# ultrasonic_motion_sensor.net
KiCad netlist of a schematic drawn in EasyEDA
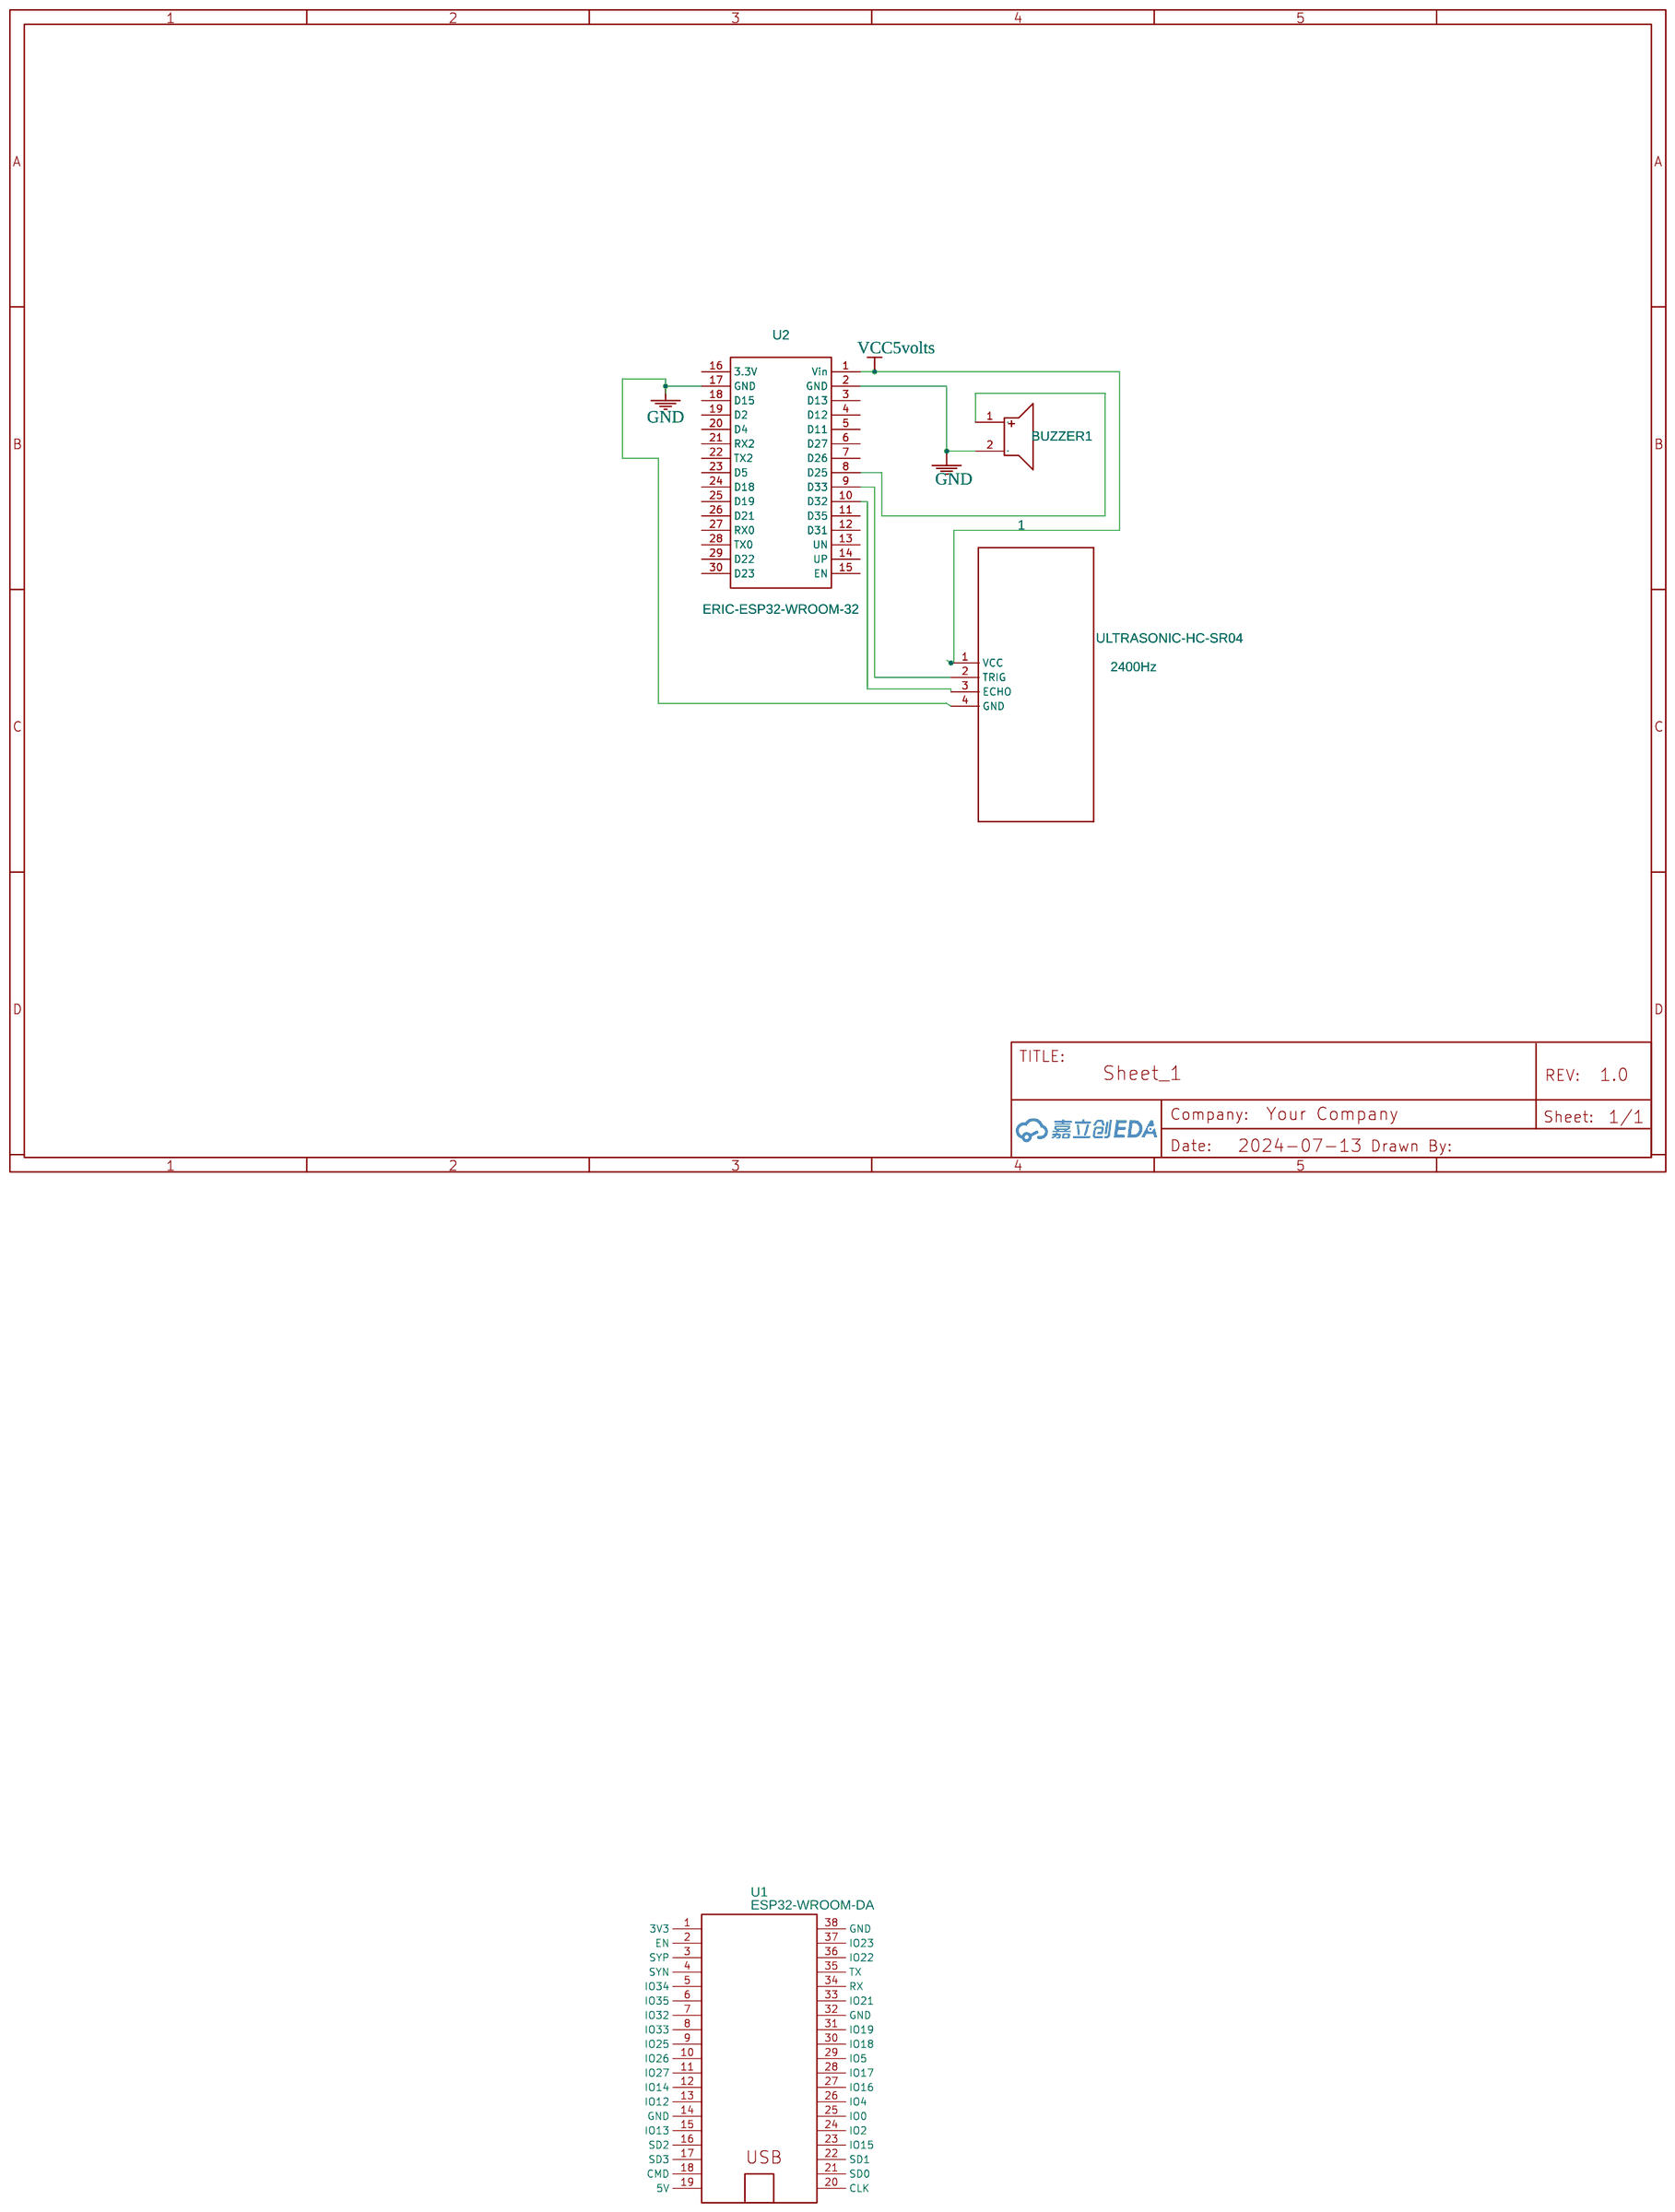
[diagram p0: schematic sheet]

(export (version "E")
  (design (tool "Eeschema 10.0.6"))
  (components
    (comp (ref "1") (value "ULTRASONIC-HC-SR04") (libsource (lib "") (part "ULTRASONIC-HC-SR04")))
    (comp (ref "BUZZER1")
      (value "2400Hz")
      (fields (field (name "Manufacturer Part") "TMB12A05") (field (name "Manufacturer") "YUEXIN(悦馨)"))
      (libsource (lib "") (part "TMB12A05_C781860"))
    )
    (comp (ref "U1")
      (value "ESP32-WROOM-DA")
      (fields (field (name "BOM_Supplier Part") "ESP32"))
      (libsource (lib "") (part "ESP32-WROOM-DA"))
    )
    (comp (ref "U2")
      (value "ERIC-ESP32-WROOM-32")
      (fields (field (name "BOM_Supplier Part") "ESP32-WROOM-32"))
      (libsource (lib "") (part "ESP32-WROOM-32"))
    )
  )
  (nets
    (net (code "1") (name "GND") (class "Default")
      (node (ref "1") (pin "4") (pinfunction "GND_4") (pintype "bidirectional"))
      (node (ref "BUZZER1") (pin "2") (pinfunction "2_2") (pintype "unspecified"))
      (node (ref "U2") (pin "17") (pinfunction "GND_17") (pintype "unspecified"))
      (node (ref "U2") (pin "2") (pinfunction "GND_2") (pintype "unspecified"))
    )
    (net (code "2") (name "Net-(1-ECHO)") (class "Default")
      (node (ref "1") (pin "3") (pinfunction "ECHO_3") (pintype "bidirectional"))
      (node (ref "U2") (pin "10") (pinfunction "D32_10") (pintype "unspecified"))
    )
    (net (code "3") (name "Net-(1-TRIG)") (class "Default")
      (node (ref "1") (pin "2") (pinfunction "TRIG_2") (pintype "bidirectional"))
      (node (ref "U2") (pin "9") (pinfunction "D33_9") (pintype "unspecified"))
    )
    (net (code "4") (name "Net-(U2-D25)") (class "Default")
      (node (ref "BUZZER1") (pin "1") (pinfunction "1_1") (pintype "unspecified"))
      (node (ref "U2") (pin "8") (pinfunction "D25_8") (pintype "unspecified"))
    )
    (net (code "5") (name "VCC5volts") (class "Default")
      (node (ref "1") (pin "1") (pinfunction "VCC_1") (pintype "bidirectional"))
      (node (ref "U2") (pin "1") (pinfunction "Vin_1") (pintype "unspecified"))
    )
    (net (code "6") (name "unconnected-(U1-3V3-Pad1)") (class "Default")
      (node (ref "U1") (pin "1") (pinfunction "3V3_1") (pintype "unspecified"))
    )
    (net (code "7") (name "unconnected-(U1-5V-Pad19)") (class "Default")
      (node (ref "U1") (pin "19") (pinfunction "5V_19") (pintype "unspecified"))
    )
    (net (code "8") (name "unconnected-(U1-CLK-Pad20)") (class "Default")
      (node (ref "U1") (pin "20") (pinfunction "CLK_20") (pintype "unspecified"))
    )
    (net (code "9") (name "unconnected-(U1-CMD-Pad18)") (class "Default")
      (node (ref "U1") (pin "18") (pinfunction "CMD_18") (pintype "unspecified"))
    )
    (net (code "10") (name "unconnected-(U1-EN-Pad2)") (class "Default")
      (node (ref "U1") (pin "2") (pinfunction "EN_2") (pintype "unspecified"))
    )
    (net (code "11") (name "unconnected-(U1-GND-Pad14)") (class "Default")
      (node (ref "U1") (pin "14") (pinfunction "GND_14") (pintype "unspecified"))
    )
    (net (code "12") (name "unconnected-(U1-GND-Pad32)") (class "Default")
      (node (ref "U1") (pin "32") (pinfunction "GND_32") (pintype "unspecified"))
    )
    (net (code "13") (name "unconnected-(U1-GND-Pad38)") (class "Default")
      (node (ref "U1") (pin "38") (pinfunction "GND_38") (pintype "unspecified"))
    )
    (net (code "14") (name "unconnected-(U1-IO0-Pad25)") (class "Default")
      (node (ref "U1") (pin "25") (pinfunction "IO0_25") (pintype "unspecified"))
    )
    (net (code "15") (name "unconnected-(U1-IO2-Pad24)") (class "Default")
      (node (ref "U1") (pin "24") (pinfunction "IO2_24") (pintype "unspecified"))
    )
    (net (code "16") (name "unconnected-(U1-IO4-Pad26)") (class "Default")
      (node (ref "U1") (pin "26") (pinfunction "IO4_26") (pintype "unspecified"))
    )
    (net (code "17") (name "unconnected-(U1-IO5-Pad29)") (class "Default")
      (node (ref "U1") (pin "29") (pinfunction "IO5_29") (pintype "unspecified"))
    )
    (net (code "18") (name "unconnected-(U1-IO12-Pad13)") (class "Default")
      (node (ref "U1") (pin "13") (pinfunction "IO12_13") (pintype "unspecified"))
    )
    (net (code "19") (name "unconnected-(U1-IO13-Pad15)") (class "Default")
      (node (ref "U1") (pin "15") (pinfunction "IO13_15") (pintype "unspecified"))
    )
    (net (code "20") (name "unconnected-(U1-IO14-Pad12)") (class "Default")
      (node (ref "U1") (pin "12") (pinfunction "IO14_12") (pintype "unspecified"))
    )
    (net (code "21") (name "unconnected-(U1-IO15-Pad23)") (class "Default")
      (node (ref "U1") (pin "23") (pinfunction "IO15_23") (pintype "unspecified"))
    )
    (net (code "22") (name "unconnected-(U1-IO16-Pad27)") (class "Default")
      (node (ref "U1") (pin "27") (pinfunction "IO16_27") (pintype "unspecified"))
    )
    (net (code "23") (name "unconnected-(U1-IO17-Pad28)") (class "Default")
      (node (ref "U1") (pin "28") (pinfunction "IO17_28") (pintype "unspecified"))
    )
    (net (code "24") (name "unconnected-(U1-IO18-Pad30)") (class "Default")
      (node (ref "U1") (pin "30") (pinfunction "IO18_30") (pintype "unspecified"))
    )
    (net (code "25") (name "unconnected-(U1-IO19-Pad31)") (class "Default")
      (node (ref "U1") (pin "31") (pinfunction "IO19_31") (pintype "unspecified"))
    )
    (net (code "26") (name "unconnected-(U1-IO21-Pad33)") (class "Default")
      (node (ref "U1") (pin "33") (pinfunction "IO21_33") (pintype "unspecified"))
    )
    (net (code "27") (name "unconnected-(U1-IO22-Pad36)") (class "Default")
      (node (ref "U1") (pin "36") (pinfunction "IO22_36") (pintype "unspecified"))
    )
    (net (code "28") (name "unconnected-(U1-IO23-Pad37)") (class "Default")
      (node (ref "U1") (pin "37") (pinfunction "IO23_37") (pintype "unspecified"))
    )
    (net (code "29") (name "unconnected-(U1-IO25-Pad9)") (class "Default")
      (node (ref "U1") (pin "9") (pinfunction "IO25_9") (pintype "unspecified"))
    )
    (net (code "30") (name "unconnected-(U1-IO26-Pad10)") (class "Default")
      (node (ref "U1") (pin "10") (pinfunction "IO26_10") (pintype "unspecified"))
    )
    (net (code "31") (name "unconnected-(U1-IO27-Pad11)") (class "Default")
      (node (ref "U1") (pin "11") (pinfunction "IO27_11") (pintype "unspecified"))
    )
    (net (code "32") (name "unconnected-(U1-IO32-Pad7)") (class "Default")
      (node (ref "U1") (pin "7") (pinfunction "IO32_7") (pintype "unspecified"))
    )
    (net (code "33") (name "unconnected-(U1-IO33-Pad8)") (class "Default")
      (node (ref "U1") (pin "8") (pinfunction "IO33_8") (pintype "unspecified"))
    )
    (net (code "34") (name "unconnected-(U1-IO34-Pad5)") (class "Default")
      (node (ref "U1") (pin "5") (pinfunction "IO34_5") (pintype "unspecified"))
    )
    (net (code "35") (name "unconnected-(U1-IO35-Pad6)") (class "Default")
      (node (ref "U1") (pin "6") (pinfunction "IO35_6") (pintype "unspecified"))
    )
    (net (code "36") (name "unconnected-(U1-RX-Pad34)") (class "Default")
      (node (ref "U1") (pin "34") (pinfunction "RX_34") (pintype "unspecified"))
    )
    (net (code "37") (name "unconnected-(U1-SD0-Pad21)") (class "Default")
      (node (ref "U1") (pin "21") (pinfunction "SD0_21") (pintype "unspecified"))
    )
    (net (code "38") (name "unconnected-(U1-SD1-Pad22)") (class "Default")
      (node (ref "U1") (pin "22") (pinfunction "SD1_22") (pintype "unspecified"))
    )
    (net (code "39") (name "unconnected-(U1-SD2-Pad16)") (class "Default")
      (node (ref "U1") (pin "16") (pinfunction "SD2_16") (pintype "unspecified"))
    )
    (net (code "40") (name "unconnected-(U1-SD3-Pad17)") (class "Default")
      (node (ref "U1") (pin "17") (pinfunction "SD3_17") (pintype "unspecified"))
    )
    (net (code "41") (name "unconnected-(U1-SYN-Pad4)") (class "Default")
      (node (ref "U1") (pin "4") (pinfunction "SYN_4") (pintype "unspecified"))
    )
    (net (code "42") (name "unconnected-(U1-SYP-Pad3)") (class "Default")
      (node (ref "U1") (pin "3") (pinfunction "SYP_3") (pintype "unspecified"))
    )
    (net (code "43") (name "unconnected-(U1-TX-Pad35)") (class "Default")
      (node (ref "U1") (pin "35") (pinfunction "TX_35") (pintype "unspecified"))
    )
    (net (code "44") (name "unconnected-(U2-3.3V-Pad16)") (class "Default")
      (node (ref "U2") (pin "16") (pinfunction "3.3V_16") (pintype "unspecified"))
    )
    (net (code "45") (name "unconnected-(U2-D2-Pad19)") (class "Default")
      (node (ref "U2") (pin "19") (pinfunction "D2_19") (pintype "unspecified"))
    )
    (net (code "46") (name "unconnected-(U2-D4-Pad20)") (class "Default")
      (node (ref "U2") (pin "20") (pinfunction "D4_20") (pintype "unspecified"))
    )
    (net (code "47") (name "unconnected-(U2-D5-Pad23)") (class "Default")
      (node (ref "U2") (pin "23") (pinfunction "D5_23") (pintype "unspecified"))
    )
    (net (code "48") (name "unconnected-(U2-D11-Pad5)") (class "Default")
      (node (ref "U2") (pin "5") (pinfunction "D11_5") (pintype "unspecified"))
    )
    (net (code "49") (name "unconnected-(U2-D12-Pad4)") (class "Default")
      (node (ref "U2") (pin "4") (pinfunction "D12_4") (pintype "unspecified"))
    )
    (net (code "50") (name "unconnected-(U2-D13-Pad3)") (class "Default")
      (node (ref "U2") (pin "3") (pinfunction "D13_3") (pintype "unspecified"))
    )
    (net (code "51") (name "unconnected-(U2-D15-Pad18)") (class "Default")
      (node (ref "U2") (pin "18") (pinfunction "D15_18") (pintype "unspecified"))
    )
    (net (code "52") (name "unconnected-(U2-D18-Pad24)") (class "Default")
      (node (ref "U2") (pin "24") (pinfunction "D18_24") (pintype "unspecified"))
    )
    (net (code "53") (name "unconnected-(U2-D19-Pad25)") (class "Default")
      (node (ref "U2") (pin "25") (pinfunction "D19_25") (pintype "unspecified"))
    )
    (net (code "54") (name "unconnected-(U2-D21-Pad26)") (class "Default")
      (node (ref "U2") (pin "26") (pinfunction "D21_26") (pintype "unspecified"))
    )
    (net (code "55") (name "unconnected-(U2-D22-Pad29)") (class "Default")
      (node (ref "U2") (pin "29") (pinfunction "D22_29") (pintype "unspecified"))
    )
    (net (code "56") (name "unconnected-(U2-D23-Pad30)") (class "Default")
      (node (ref "U2") (pin "30") (pinfunction "D23_30") (pintype "unspecified"))
    )
    (net (code "57") (name "unconnected-(U2-D26-Pad7)") (class "Default")
      (node (ref "U2") (pin "7") (pinfunction "D26_7") (pintype "unspecified"))
    )
    (net (code "58") (name "unconnected-(U2-D27-Pad6)") (class "Default")
      (node (ref "U2") (pin "6") (pinfunction "D27_6") (pintype "unspecified"))
    )
    (net (code "59") (name "unconnected-(U2-D31-Pad12)") (class "Default")
      (node (ref "U2") (pin "12") (pinfunction "D31_12") (pintype "unspecified"))
    )
    (net (code "60") (name "unconnected-(U2-D35-Pad11)") (class "Default")
      (node (ref "U2") (pin "11") (pinfunction "D35_11") (pintype "unspecified"))
    )
    (net (code "61") (name "unconnected-(U2-EN-Pad15)") (class "Default")
      (node (ref "U2") (pin "15") (pinfunction "EN_15") (pintype "unspecified"))
    )
    (net (code "62") (name "unconnected-(U2-RX0-Pad27)") (class "Default")
      (node (ref "U2") (pin "27") (pinfunction "RX0_27") (pintype "unspecified"))
    )
    (net (code "63") (name "unconnected-(U2-RX2-Pad21)") (class "Default")
      (node (ref "U2") (pin "21") (pinfunction "RX2_21") (pintype "unspecified"))
    )
    (net (code "64") (name "unconnected-(U2-TX0-Pad28)") (class "Default")
      (node (ref "U2") (pin "28") (pinfunction "TX0_28") (pintype "unspecified"))
    )
    (net (code "65") (name "unconnected-(U2-TX2-Pad22)") (class "Default")
      (node (ref "U2") (pin "22") (pinfunction "TX2_22") (pintype "unspecified"))
    )
    (net (code "66") (name "unconnected-(U2-UN-Pad13)") (class "Default")
      (node (ref "U2") (pin "13") (pinfunction "UN_13") (pintype "unspecified"))
    )
    (net (code "67") (name "unconnected-(U2-UP-Pad14)") (class "Default")
      (node (ref "U2") (pin "14") (pinfunction "UP_14") (pintype "unspecified"))
    )
  )
)
